# Main.net
KiCad netlist of a schematic drawn in Altium Designer
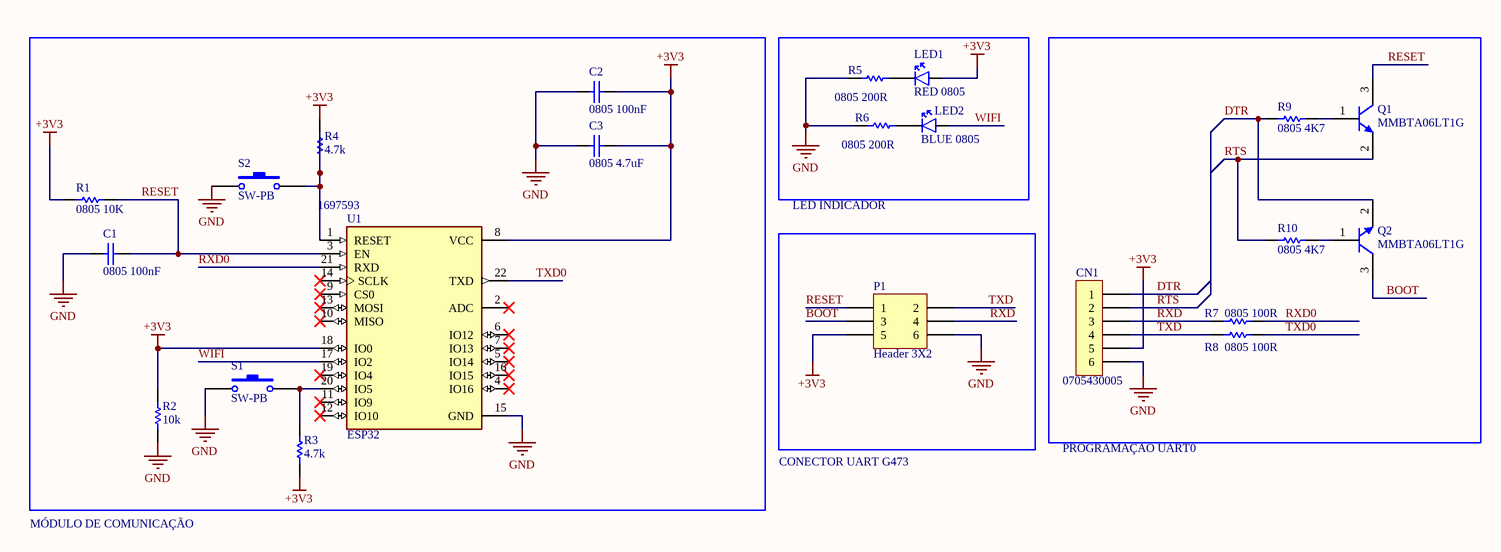
[diagram p0: Main.SchDoc]

(export (version "E")
  (design (tool "Eeschema 10.0.6"))
  (components
    (comp (ref "C1")
      (value "0805 100nF")
      (footprint "CAP0805")
      (description "CC Series 0805 0.1 uF 50 V ±10 % Tolerance X7R SMT Multilayer Ceramic Capacitor")
      (fields
        (field (name "MANUFACTURER") "Yageo")
        (field (name "MANUFACTURER PART NUMBER") "CC0805KRX7R9BB104")
      )
      (libsource (lib "occhi") (part "CC0805KRX7R9BB104"))
    )
    (comp (ref "C2")
      (value "0805 100nF")
      (footprint "CAP0805")
      (description "CC Series 0805 0.1 uF 50 V ±10 % Tolerance X7R SMT Multilayer Ceramic Capacitor")
      (fields
        (field (name "MANUFACTURER") "Yageo")
        (field (name "MANUFACTURER PART NUMBER") "CC0805KRX7R9BB104")
      )
      (libsource (lib "occhi") (part "CC0805KRX7R9BB104"))
    )
    (comp (ref "C3")
      (value "0805 4.7uF")
      (footprint "CAP0805")
      (description "4.7uF ±10% 50V 0805")
      (fields
        (field (name "MANUFACTURER") "TDK")
        (field (name "MANUFACTURER PART NUMBER") "C2012X5R1H475K125AB")
      )
      (libsource (lib "occhi") (part "C2012X5R1H475K125AB"))
    )
    (comp (ref "CN1")
      (value "0705430005")
      (footprint "FP-0705430005-MFG")
      (description "Conn Shrouded Header (4 Sides) HDR 6 POS 2.54mm Solder ST Top Entry Thru-Hole SL™ Tube")
      (fields (field (name "MANUFACTURER") "Molex"))
      (libsource (lib "occhi") (part "0705430005"))
    )
    (comp (ref "LED1")
      (value "RED 0805")
      (footprint "LEDC2012X80N")
      (description "Red SMD 625nm LED Indication - Discrete 2V 0805 (2012 Metric)")
      (fields
        (field (name "MANUFACTURER_PART_NUMBER") "150080RS75000")
        (field (name "MOUSER PART NUMBER") "710-150080RS75000")
      )
      (libsource (lib "occhi") (part "150080RS75000"))
    )
    (comp (ref "LED2")
      (value "BLUE 0805")
      (footprint "LEDC2012X80N")
      (description "Red SMD 625nm LED Indication - Discrete 2V 0805 (2012 Metric)")
      (fields
        (field (name "MANUFACTURER_PART_NUMBER") "150080RS75000")
        (field (name "MOUSER PART NUMBER") "710-150080RS75000")
      )
      (libsource (lib "occhi") (part "150080RS75000"))
    )
    (comp (ref "P1")
      (value "Header 3X2")
      (footprint "HDR2X3M")
      (description "Header, 3-Pin, Dual row")
      (fields (field (name "PUBLISHER") "Altium Limited"))
      (libsource (lib "Connectors Library") (part "Header 3X2"))
    )
    (comp (ref "Q1")
      (value "MMBTA06LT1G")
      (footprint "ONSC-SOT-23-3-318-08_V")
      (description "Trans GP BJT NPN 80V 0.5A 3-Pin SOT-23 T/R")
      (fields (field (name "MANUFACTURER") "ON Semiconductor"))
      (libsource (lib "occhi") (part "MMBTA06LT1G"))
    )
    (comp (ref "Q2")
      (value "MMBTA06LT1G")
      (footprint "ONSC-SOT-23-3-318-08_V")
      (description "Trans GP BJT NPN 80V 0.5A 3-Pin SOT-23 T/R")
      (fields (field (name "MANUFACTURER") "ON Semiconductor"))
      (libsource (lib "occhi") (part "MMBTA06LT1G"))
    )
    (comp (ref "R1")
      (value "0805 10K")
      (footprint "RES0805")
      (description "10K Omhs 0805 ± 1.00% 0.125W ± 100ppm/℃")
      (fields
        (field (name "MANUFACTURER") "Yageo")
        (field (name "MANUFACTURER PART NUMBER") "RC0603FR-0710KL")
      )
      (libsource (lib "occhi") (part "RC0805FR-0710KL"))
    )
    (comp (ref "R2")
      (value "10k")
      (footprint "R1608[0603]")
      (description "Res, 10K, 0.01%, 0.25W, 1206, Metal Foil")
      (fields (field (name "MANUFACTURER PART NUMBER") "Y163010K0000T9R") (field (name "TOLERANCE") "0.01%"))
      (libsource (lib "Basic Library") (part "R"))
    )
    (comp (ref "R3")
      (value "4.7k")
      (footprint "R1005[0402]")
      (description "Res Thick Film 1206 4.7K Ohm 5% 1/4W ±200ppm/°C Molded SMD Punched Carrier T/R")
      (fields (field (name "MANUFACTURER PART NUMBER") "ERJ-8GEYJ472V") (field (name "TOLERANCE") "5%"))
      (libsource (lib "Basic Library") (part "R"))
    )
    (comp (ref "R4")
      (value "4.7k")
      (footprint "R1005[0402]")
      (description "Res Thick Film 1206 4.7K Ohm 5% 1/4W ±200ppm/°C Molded SMD Punched Carrier T/R")
      (fields (field (name "MANUFACTURER PART NUMBER") "ERJ-8GEYJ472V") (field (name "TOLERANCE") "5%"))
      (libsource (lib "Basic Library") (part "R"))
    )
    (comp (ref "R5")
      (value "0805 200R")
      (footprint "RES0805")
      (description "200 Ohm  0805 ± 1.00% 0.125W ± 100ppm/℃")
      (fields
        (field (name "MANUFACTURER") "Yageo")
        (field (name "MANUFACTURER PART NUMBER") "RC0603FR-07200RL")
      )
      (libsource (lib "occhi") (part "RC0805FR-07200RL"))
    )
    (comp (ref "R6")
      (value "0805 200R")
      (footprint "RES0805")
      (description "200 Ohm  0805 ± 1.00% 0.125W ± 100ppm/℃")
      (fields
        (field (name "MANUFACTURER") "Yageo")
        (field (name "MANUFACTURER PART NUMBER") "RC0603FR-07200RL")
      )
      (libsource (lib "occhi") (part "RC0805FR-07200RL"))
    )
    (comp (ref "R7")
      (value "0805 100R")
      (footprint "RES0805")
      (description "100R ± 1.00% 0.125W ± 100ppm/℃ 0805")
      (fields
        (field (name "MANUFACTURER") "Yageo")
        (field (name "MANUFACTURER PART NUMBER") "RC0805FR-07100RL")
      )
      (libsource (lib "occhi") (part "RC0805FR-07100RL"))
    )
    (comp (ref "R8")
      (value "0805 100R")
      (footprint "RES0805")
      (description "100R ± 1.00% 0.125W ± 100ppm/℃ 0805")
      (fields
        (field (name "MANUFACTURER") "Yageo")
        (field (name "MANUFACTURER PART NUMBER") "RC0805FR-07100RL")
      )
      (libsource (lib "occhi") (part "RC0805FR-07100RL"))
    )
    (comp (ref "R9")
      (value "0805 4K7")
      (footprint "RES0805")
      (description "4700Ω ± 1.00% 0.125W ± 100ppm/℃ 0805")
      (fields
        (field (name "MANUFACTURER") "Yageo")
        (field (name "MANUFACTURER PART NUMBER") "RC0805FR-074K7L")
      )
      (libsource (lib "occhi") (part "RC0805FR-074K7L"))
    )
    (comp (ref "R10")
      (value "0805 4K7")
      (footprint "RES0805")
      (description "4700Ω ± 1.00% 0.125W ± 100ppm/℃ 0805")
      (fields
        (field (name "MANUFACTURER") "Yageo")
        (field (name "MANUFACTURER PART NUMBER") "RC0805FR-074K7L")
      )
      (libsource (lib "occhi") (part "RC0805FR-074K7L"))
    )
    (comp (ref "S1")
      (value "SW-PB")
      (footprint "PB-SW")
      (description "Tactile Switch")
      (libsource (lib "Basic Library") (part "SW Tact"))
    )
    (comp (ref "S2")
      (value "SW-PB")
      (footprint "PB-SW")
      (description "Tactile Switch")
      (libsource (lib "Basic Library") (part "SW Tact"))
    )
    (comp (ref "U1")
      (value "ESP32")
      (footprint "XCVR_ESP8266-12E/ESP-12E")
      (fields
        (field (name "MP") "ESP8266-12E/ESP-12E")
        (field (name "MF") "AI-Thinker")
        (field (name "SUPPLIER PART NUMBER 1") "1697593")
      )
      (libsource (lib "ESP8266-12E_ESP-12E") (part "ESP8266-12E/ESP-12E"))
    )
  )
  (nets
    (net (code "1") (name "+3V3") (class "Default")
      (node (ref "C2") (pin "2") (pinfunction "2_2") (pintype "passive"))
      (node (ref "C3") (pin "2") (pinfunction "2_2") (pintype "passive"))
      (node (ref "CN1") (pin "5") (pinfunction "5_5") (pintype "passive"))
      (node (ref "LED1") (pin "2") (pinfunction "A_2") (pintype "passive"))
      (node (ref "P1") (pin "5") (pinfunction "5_5") (pintype "passive"))
      (node (ref "R1") (pin "1") (pinfunction "1_1") (pintype "passive"))
      (node (ref "R2") (pin "2") (pinfunction "2_2") (pintype "passive"))
      (node (ref "R3") (pin "2") (pinfunction "2_2") (pintype "passive"))
      (node (ref "R4") (pin "2") (pinfunction "2_2") (pintype "passive"))
      (node (ref "U1") (pin "18") (pinfunction "IO0_18") (pintype "bidirectional"))
      (node (ref "U1") (pin "8") (pinfunction "VCC_8") (pintype "power_in"))
    )
    (net (code "2") (name "/BOOT") (class "Default")
      (node (ref "P1") (pin "3") (pinfunction "3_3") (pintype "passive"))
      (node (ref "Q2") (pin "3") (pinfunction "C_3") (pintype "passive"))
    )
    (net (code "3") (name "/DTR") (class "Default")
      (node (ref "CN1") (pin "1") (pinfunction "1_1") (pintype "passive"))
      (node (ref "Q2") (pin "2") (pinfunction "E_2") (pintype "passive"))
      (node (ref "R9") (pin "1") (pinfunction "1_1") (pintype "passive"))
    )
    (net (code "4") (name "/RESET") (class "Default")
      (node (ref "C1") (pin "2") (pinfunction "2_2") (pintype "passive"))
      (node (ref "P1") (pin "1") (pinfunction "1_1") (pintype "passive"))
      (node (ref "Q1") (pin "3") (pinfunction "C_3") (pintype "passive"))
      (node (ref "R1") (pin "2") (pinfunction "2_2") (pintype "passive"))
      (node (ref "U1") (pin "3") (pinfunction "EN_3") (pintype "input"))
    )
    (net (code "5") (name "/RTS") (class "Default")
      (node (ref "CN1") (pin "2") (pinfunction "2_2") (pintype "passive"))
      (node (ref "Q1") (pin "2") (pinfunction "E_2") (pintype "passive"))
      (node (ref "R10") (pin "1") (pinfunction "1_1") (pintype "passive"))
    )
    (net (code "6") (name "/RXD") (class "Default")
      (node (ref "CN1") (pin "3") (pinfunction "3_3") (pintype "passive"))
      (node (ref "P1") (pin "4") (pinfunction "4_4") (pintype "passive"))
      (node (ref "R7") (pin "1") (pinfunction "1_1") (pintype "passive"))
    )
    (net (code "7") (name "/RXD0") (class "Default")
      (node (ref "R7") (pin "2") (pinfunction "2_2") (pintype "passive"))
      (node (ref "U1") (pin "21") (pinfunction "RXD_21") (pintype "input"))
    )
    (net (code "8") (name "/TXD") (class "Default")
      (node (ref "CN1") (pin "4") (pinfunction "4_4") (pintype "passive"))
      (node (ref "P1") (pin "2") (pinfunction "2_2") (pintype "passive"))
      (node (ref "R8") (pin "1") (pinfunction "1_1") (pintype "passive"))
    )
    (net (code "9") (name "/TXD0") (class "Default")
      (node (ref "R8") (pin "2") (pinfunction "2_2") (pintype "passive"))
      (node (ref "U1") (pin "22") (pinfunction "TXD_22") (pintype "output"))
    )
    (net (code "10") (name "/WIFI") (class "Default")
      (node (ref "LED2") (pin "2") (pinfunction "A_2") (pintype "passive"))
      (node (ref "U1") (pin "17") (pinfunction "IO2_17") (pintype "bidirectional"))
    )
    (net (code "11") (name "GND") (class "Default")
      (node (ref "C1") (pin "1") (pinfunction "1_1") (pintype "passive"))
      (node (ref "C2") (pin "1") (pinfunction "1_1") (pintype "passive"))
      (node (ref "C3") (pin "1") (pinfunction "1_1") (pintype "passive"))
      (node (ref "CN1") (pin "6") (pinfunction "6_6") (pintype "passive"))
      (node (ref "P1") (pin "6") (pinfunction "6_6") (pintype "passive"))
      (node (ref "R2") (pin "1") (pinfunction "1_1") (pintype "passive"))
      (node (ref "R5") (pin "1") (pinfunction "1_1") (pintype "passive"))
      (node (ref "R6") (pin "1") (pinfunction "1_1") (pintype "passive"))
      (node (ref "S1") (pin "1") (pinfunction "1_1") (pintype "passive"))
      (node (ref "S2") (pin "1") (pinfunction "1_1") (pintype "passive"))
      (node (ref "U1") (pin "15") (pinfunction "GND_15") (pintype "power_in"))
    )
    (net (code "12") (name "Net-(LED1-K)") (class "Default")
      (node (ref "LED1") (pin "1") (pinfunction "K_1") (pintype "passive"))
      (node (ref "R5") (pin "2") (pinfunction "2_2") (pintype "passive"))
    )
    (net (code "13") (name "Net-(LED2-K)") (class "Default")
      (node (ref "LED2") (pin "1") (pinfunction "K_1") (pintype "passive"))
      (node (ref "R6") (pin "2") (pinfunction "2_2") (pintype "passive"))
    )
    (net (code "14") (name "Net-(Q1-B)") (class "Default")
      (node (ref "Q1") (pin "1") (pinfunction "B_1") (pintype "passive"))
      (node (ref "R9") (pin "2") (pinfunction "2_2") (pintype "passive"))
    )
    (net (code "15") (name "Net-(Q2-B)") (class "Default")
      (node (ref "Q2") (pin "1") (pinfunction "B_1") (pintype "passive"))
      (node (ref "R10") (pin "2") (pinfunction "2_2") (pintype "passive"))
    )
    (net (code "16") (name "Net-(U1-IO5)") (class "Default")
      (node (ref "R3") (pin "1") (pinfunction "1_1") (pintype "passive"))
      (node (ref "S1") (pin "2") (pinfunction "2_2") (pintype "passive"))
      (node (ref "U1") (pin "20") (pinfunction "IO5_20") (pintype "bidirectional"))
    )
    (net (code "17") (name "Net-(U1-RESET)") (class "Default")
      (node (ref "R4") (pin "1") (pinfunction "1_1") (pintype "passive"))
      (node (ref "S2") (pin "2") (pinfunction "2_2") (pintype "passive"))
      (node (ref "U1") (pin "1") (pinfunction "RESET_1") (pintype "input"))
    )
    (net (code "18") (name "unconnected-(U1-ADC-Pad2)") (class "Default")
      (node (ref "U1") (pin "2") (pinfunction "ADC_2") (pintype "passive+no_connect"))
    )
    (net (code "19") (name "unconnected-(U1-CS0-Pad9)") (class "Default")
      (node (ref "U1") (pin "9") (pinfunction "CS0_9") (pintype "input+no_connect"))
    )
    (net (code "20") (name "unconnected-(U1-IO4-Pad19)") (class "Default")
      (node (ref "U1") (pin "19") (pinfunction "IO4_19") (pintype "bidirectional+no_connect"))
    )
    (net (code "21") (name "unconnected-(U1-IO9-Pad11)") (class "Default")
      (node (ref "U1") (pin "11") (pinfunction "IO9_11") (pintype "bidirectional+no_connect"))
    )
    (net (code "22") (name "unconnected-(U1-IO10-Pad12)") (class "Default")
      (node (ref "U1") (pin "12") (pinfunction "IO10_12") (pintype "bidirectional+no_connect"))
    )
    (net (code "23") (name "unconnected-(U1-IO12-Pad6)") (class "Default")
      (node (ref "U1") (pin "6") (pinfunction "IO12_6") (pintype "bidirectional+no_connect"))
    )
    (net (code "24") (name "unconnected-(U1-IO13-Pad7)") (class "Default")
      (node (ref "U1") (pin "7") (pinfunction "IO13_7") (pintype "bidirectional+no_connect"))
    )
    (net (code "25") (name "unconnected-(U1-IO14-Pad5)") (class "Default")
      (node (ref "U1") (pin "5") (pinfunction "IO14_5") (pintype "bidirectional+no_connect"))
    )
    (net (code "26") (name "unconnected-(U1-IO15-Pad16)") (class "Default")
      (node (ref "U1") (pin "16") (pinfunction "IO15_16") (pintype "bidirectional+no_connect"))
    )
    (net (code "27") (name "unconnected-(U1-IO16-Pad4)") (class "Default")
      (node (ref "U1") (pin "4") (pinfunction "IO16_4") (pintype "bidirectional+no_connect"))
    )
    (net (code "28") (name "unconnected-(U1-MISO-Pad10)") (class "Default")
      (node (ref "U1") (pin "10") (pinfunction "MISO_10") (pintype "bidirectional+no_connect"))
    )
    (net (code "29") (name "unconnected-(U1-MOSI-Pad13)") (class "Default")
      (node (ref "U1") (pin "13") (pinfunction "MOSI_13") (pintype "bidirectional+no_connect"))
    )
    (net (code "30") (name "unconnected-(U1-SCLK-Pad14)") (class "Default")
      (node (ref "U1") (pin "14") (pinfunction "SCLK_14") (pintype "input+no_connect"))
    )
  )
)
